# ADC.net
KiCad netlist of a schematic drawn in Altium Designer
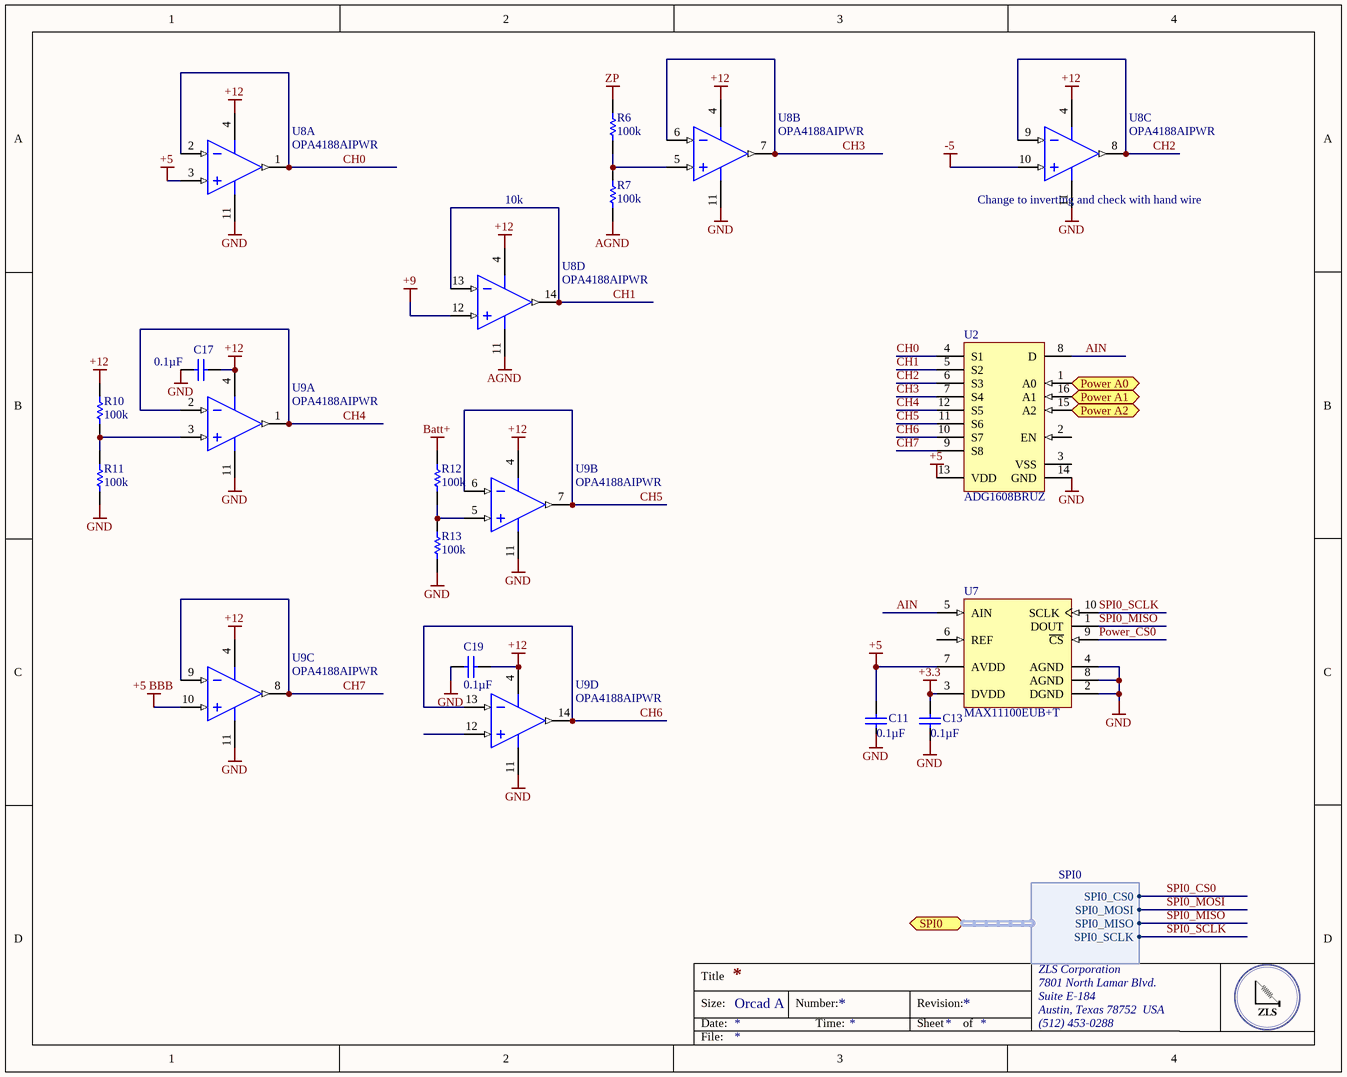
[diagram p0: ADC.SchDoc]

(export (version "E")
  (design (tool "Eeschema 10.0.6"))
  (components
    (comp (ref "C11")
      (value "CAP CER 0.1UF 25V X7R 0805")
      (footprint "CAPC0805(2012)145_N")
      (fields
        (field (name "MANUFACTURER") "Murata Electronics North America")
        (field (name "MANUFACTURER PART NUMBER") "GRM21BR71E104KA01L")
        (field (name "CAPACITANCE") "0.1µF")
        (field (name "TOLERANCE") "±10%")
      )
      (libsource (lib "Altium Content Vault") (part "CMP-1036-04795-1"))
    )
    (comp (ref "C13")
      (value "CAP CER 0.1UF 25V X7R 0805")
      (footprint "CAPC0805(2012)145_N")
      (fields
        (field (name "MANUFACTURER") "Murata Electronics North America")
        (field (name "MANUFACTURER PART NUMBER") "GRM21BR71E104KA01L")
        (field (name "CAPACITANCE") "0.1µF")
        (field (name "TOLERANCE") "±10%")
      )
      (libsource (lib "Altium Content Vault") (part "CMP-1036-04795-1"))
    )
    (comp (ref "C17")
      (value "CAP CER 0.1UF 16V X7R 0805")
      (footprint "CAPC0805(2012)145_N")
      (fields
        (field (name "TOLERANCE") "±10%")
        (field (name "MANUFACTURER") "Murata Electronics North America")
        (field (name "MANUFACTURER PART NUMBER") "GRM219R71C104KA01D")
        (field (name "CAPACITANCE") "0.1µF")
      )
      (libsource (lib "Altium Content Vault") (part "CMP-1036-04795-1"))
    )
    (comp (ref "C19")
      (value "CAP CER 0.1UF 16V X7R 0805")
      (footprint "CAPC0805(2012)145_N")
      (fields
        (field (name "TOLERANCE") "±10%")
        (field (name "MANUFACTURER") "Murata Electronics North America")
        (field (name "MANUFACTURER PART NUMBER") "GRM219R71C104KA01D")
        (field (name "CAPACITANCE") "0.1µF")
      )
      (libsource (lib "Altium Content Vault") (part "CMP-1036-04795-1"))
    )
    (comp (ref "R6")
      (value "100k")
      (footprint "RESC0402(1005)_M")
      (libsource (lib "Altium Content Vault") (part "CMP-1011-00651-1"))
    )
    (comp (ref "R7")
      (value "100k")
      (footprint "RESC0402(1005)_M")
      (libsource (lib "Altium Content Vault") (part "CMP-1011-00651-1"))
    )
    (comp (ref "R10")
      (value "100k")
      (footprint "RESC0402(1005)_M")
      (libsource (lib "Altium Content Vault") (part "CMP-1011-00651-1"))
    )
    (comp (ref "R11")
      (value "100k")
      (footprint "RESC0402(1005)_M")
      (libsource (lib "Altium Content Vault") (part "CMP-1011-00651-1"))
    )
    (comp (ref "R12")
      (value "100k")
      (footprint "RESC0402(1005)_M")
      (libsource (lib "Altium Content Vault") (part "CMP-1011-00651-1"))
    )
    (comp (ref "R13")
      (value "100k")
      (footprint "RESC0402(1005)_M")
      (libsource (lib "Altium Content Vault") (part "CMP-1011-00651-1"))
    )
    (comp (ref "U2")
      (value "ADG1608BRUZ")
      (footprint "ADI-RU-16_M")
      (description "4.5 Ohm Ron, 8-Channel +/-5 V,+12 V, +5 V and +3.3 V Multiplexer, 16-pin SOP (RU-16), Tube")
      (fields (field (name "MANUFACTURER") "Analog Devices"))
      (libsource (lib "Altium Content Vault") (part "ADI-ADG1608-RU-16"))
    )
    (comp (ref "U7")
      (value "MAX11100EUB+T")
      (footprint "U10+2_L")
      (description "16-Bit, +5V, 200ksps ADC with 10uA Shutdown, 10-Pin uMAX, -40°C to +85°C, Pb-Free, Tape and Reel")
      (libsource (lib "Altium Content Vault") (part "CON-ADC-MAX11100-IL10"))
    )
    (comp (ref "U8")
      (value "OPA4188AIPWR")
      (footprint "PW0014A_N")
      (fields (field (name "MANUFACTURER") "Texas Instruments"))
      (libsource (lib "Altium Content Vault") (part "TI-OPA4188-PW14"))
    )
    (comp (ref "U9")
      (value "OPA4188AIPWR")
      (footprint "PW0014A_N")
      (fields (field (name "MANUFACTURER") "Texas Instruments"))
      (libsource (lib "Altium Content Vault") (part "TI-OPA4188-PW14"))
    )
  )
  (nets
    (net (code "2") (name "+3.3") (class "Default")
      (node (ref "C13") (pin "1") (pinfunction "1_1") (pintype "passive"))
      (node (ref "U7") (pin "3") (pinfunction "DVDD_3") (pintype "power_in"))
    )
    (net (code "3") (name "+5") (class "Default")
      (node (ref "C11") (pin "1") (pinfunction "1_1") (pintype "passive"))
      (node (ref "U2") (pin "13") (pinfunction "VDD_13") (pintype "power_in"))
      (node (ref "U7") (pin "7") (pinfunction "AVDD_7") (pintype "power_in"))
      (node (ref "U8") (pin "3") (pinfunction "IN_A+_3") (pintype "input"))
    )
    (net (code "4") (name "+5 BBB") (class "Default")
      (node (ref "U9") (pin "10") (pinfunction "IN_C+_10") (pintype "input"))
    )
    (net (code "5") (name "+9") (class "Default")
      (node (ref "U8") (pin "12") (pinfunction "IN_D+_12") (pintype "input"))
    )
    (net (code "6") (name "+12") (class "Default")
      (node (ref "C17") (pin "2") (pinfunction "2_2") (pintype "passive"))
      (node (ref "C19") (pin "2") (pinfunction "2_2") (pintype "passive"))
      (node (ref "R10") (pin "2") (pinfunction "2_2") (pintype "passive"))
      (node (ref "U8") (pin "4") (pinfunction "V+_4") (pintype "power_in"))
      (node (ref "U9") (pin "4") (pinfunction "V+_4") (pintype "power_in"))
    )
    (net (code "7") (name "-5") (class "Default")
      (node (ref "U8") (pin "10") (pinfunction "IN_C+_10") (pintype "input"))
    )
    (net (code "8") (name "/AIN") (class "Default")
      (node (ref "U2") (pin "8") (pinfunction "D_8") (pintype "passive"))
      (node (ref "U7") (pin "5") (pinfunction "AIN_5") (pintype "input"))
    )
    (net (code "9") (name "/CH0") (class "Default")
      (node (ref "U2") (pin "4") (pinfunction "S1_4") (pintype "passive"))
      (node (ref "U8") (pin "1") (pinfunction "OUT_A_1") (pintype "output"))
      (node (ref "U8") (pin "2") (pinfunction "IN_A-_2") (pintype "input"))
    )
    (net (code "10") (name "/CH1") (class "Default")
      (node (ref "U2") (pin "5") (pinfunction "S2_5") (pintype "passive"))
      (node (ref "U8") (pin "13") (pinfunction "IN_D-_13") (pintype "input"))
      (node (ref "U8") (pin "14") (pinfunction "OUT_D_14") (pintype "output"))
    )
    (net (code "11") (name "/CH2") (class "Default")
      (node (ref "U2") (pin "6") (pinfunction "S3_6") (pintype "passive"))
      (node (ref "U8") (pin "8") (pinfunction "OUT_C_8") (pintype "output"))
      (node (ref "U8") (pin "9") (pinfunction "IN_C-_9") (pintype "input"))
    )
    (net (code "12") (name "/CH3") (class "Default")
      (node (ref "U2") (pin "7") (pinfunction "S4_7") (pintype "passive"))
      (node (ref "U8") (pin "6") (pinfunction "IN_B-_6") (pintype "input"))
      (node (ref "U8") (pin "7") (pinfunction "OUT_B_7") (pintype "output"))
    )
    (net (code "13") (name "/CH4") (class "Default")
      (node (ref "U2") (pin "12") (pinfunction "S5_12") (pintype "passive"))
      (node (ref "U9") (pin "1") (pinfunction "OUT_A_1") (pintype "output"))
      (node (ref "U9") (pin "2") (pinfunction "IN_A-_2") (pintype "input"))
    )
    (net (code "14") (name "/CH5") (class "Default")
      (node (ref "U2") (pin "11") (pinfunction "S6_11") (pintype "passive"))
      (node (ref "U9") (pin "6") (pinfunction "IN_B-_6") (pintype "input"))
      (node (ref "U9") (pin "7") (pinfunction "OUT_B_7") (pintype "output"))
    )
    (net (code "15") (name "/CH6") (class "Default")
      (node (ref "U2") (pin "10") (pinfunction "S7_10") (pintype "passive"))
      (node (ref "U9") (pin "13") (pinfunction "IN_D-_13") (pintype "input"))
      (node (ref "U9") (pin "14") (pinfunction "OUT_D_14") (pintype "output"))
    )
    (net (code "16") (name "/CH7") (class "Default")
      (node (ref "U2") (pin "9") (pinfunction "S8_9") (pintype "passive"))
      (node (ref "U9") (pin "8") (pinfunction "OUT_C_8") (pintype "output"))
      (node (ref "U9") (pin "9") (pinfunction "IN_C-_9") (pintype "input"))
    )
    (net (code "17") (name "/Power A0") (class "Default")
      (node (ref "U2") (pin "1") (pinfunction "A0_1") (pintype "input"))
    )
    (net (code "18") (name "/Power A1") (class "Default")
      (node (ref "U2") (pin "16") (pinfunction "A1_16") (pintype "input"))
    )
    (net (code "19") (name "/Power A2") (class "Default")
      (node (ref "U2") (pin "15") (pinfunction "A2_15") (pintype "input"))
    )
    (net (code "20") (name "/Power_CS0") (class "Default")
      (node (ref "U7") (pin "9") (pinfunction "~{CS}_9") (pintype "input"))
    )
    (net (code "22") (name "/SPI0_MISO") (class "Default")
      (node (ref "U7") (pin "1") (pinfunction "DOUT_1") (pintype "tri_state"))
    )
    (net (code "24") (name "/SPI0_SCLK") (class "Default")
      (node (ref "U7") (pin "10") (pinfunction "SCLK_10") (pintype "input"))
    )
    (net (code "26") (name "AGND") (class "Default")
      (node (ref "R7") (pin "1") (pinfunction "1_1") (pintype "passive"))
      (node (ref "U8") (pin "11") (pinfunction "V-_11") (pintype "power_in"))
    )
    (net (code "27") (name "Batt+") (class "Default")
      (node (ref "R12") (pin "2") (pinfunction "2_2") (pintype "passive"))
    )
    (net (code "28") (name "GND") (class "Default")
      (node (ref "C13") (pin "2") (pinfunction "2_2") (pintype "passive"))
      (node (ref "C17") (pin "1") (pinfunction "1_1") (pintype "passive"))
      (node (ref "C19") (pin "1") (pinfunction "1_1") (pintype "passive"))
      (node (ref "R11") (pin "1") (pinfunction "1_1") (pintype "passive"))
      (node (ref "R13") (pin "1") (pinfunction "1_1") (pintype "passive"))
      (node (ref "U2") (pin "14") (pinfunction "GND_14") (pintype "power_in"))
      (node (ref "U7") (pin "2") (pinfunction "DGND_2") (pintype "power_in"))
      (node (ref "U7") (pin "4") (pinfunction "AGND_4") (pintype "power_in"))
      (node (ref "U7") (pin "8") (pinfunction "AGND_8") (pintype "power_in"))
      (node (ref "U8") (pin "11") (pinfunction "V-_11") (pintype "power_in"))
      (node (ref "U9") (pin "11") (pinfunction "V-_11") (pintype "power_in"))
    )
    (net (code "29") (name "Net-(U8B-IN_B+)") (class "Default")
      (node (ref "R6") (pin "1") (pinfunction "1_1") (pintype "passive"))
      (node (ref "R7") (pin "2") (pinfunction "2_2") (pintype "passive"))
      (node (ref "U8") (pin "5") (pinfunction "IN_B+_5") (pintype "input"))
    )
    (net (code "30") (name "Net-(U9A-IN_A+)") (class "Default")
      (node (ref "R10") (pin "1") (pinfunction "1_1") (pintype "passive"))
      (node (ref "R11") (pin "2") (pinfunction "2_2") (pintype "passive"))
      (node (ref "U9") (pin "3") (pinfunction "IN_A+_3") (pintype "input"))
    )
    (net (code "31") (name "Net-(U9B-IN_B+)") (class "Default")
      (node (ref "R12") (pin "1") (pinfunction "1_1") (pintype "passive"))
      (node (ref "R13") (pin "2") (pinfunction "2_2") (pintype "passive"))
      (node (ref "U9") (pin "5") (pinfunction "IN_B+_5") (pintype "input"))
    )
    (net (code "32") (name "ZP") (class "Default")
      (node (ref "R6") (pin "2") (pinfunction "2_2") (pintype "passive"))
    )
    (net (code "33") (name "unconnected-(C11-Pad2)") (class "Default")
      (node (ref "C11") (pin "2") (pinfunction "2_2") (pintype "passive"))
    )
    (net (code "34") (name "unconnected-(U2-EN-Pad2)") (class "Default")
      (node (ref "U2") (pin "2") (pinfunction "EN_2") (pintype "input"))
    )
    (net (code "35") (name "unconnected-(U2-VSS-Pad3)") (class "Default")
      (node (ref "U2") (pin "3") (pinfunction "VSS_3") (pintype "power_in"))
    )
    (net (code "36") (name "unconnected-(U7-REF-Pad6)") (class "Default")
      (node (ref "U7") (pin "6") (pinfunction "REF_6") (pintype "input"))
    )
    (net (code "37") (name "unconnected-(U9D-IN_D+-Pad12)") (class "Default")
      (node (ref "U9") (pin "12") (pinfunction "IN_D+_12") (pintype "input"))
    )
  )
)
